# XRACER-SERIALS-R07.net
KiCad netlist of a schematic drawn in Altium Designer
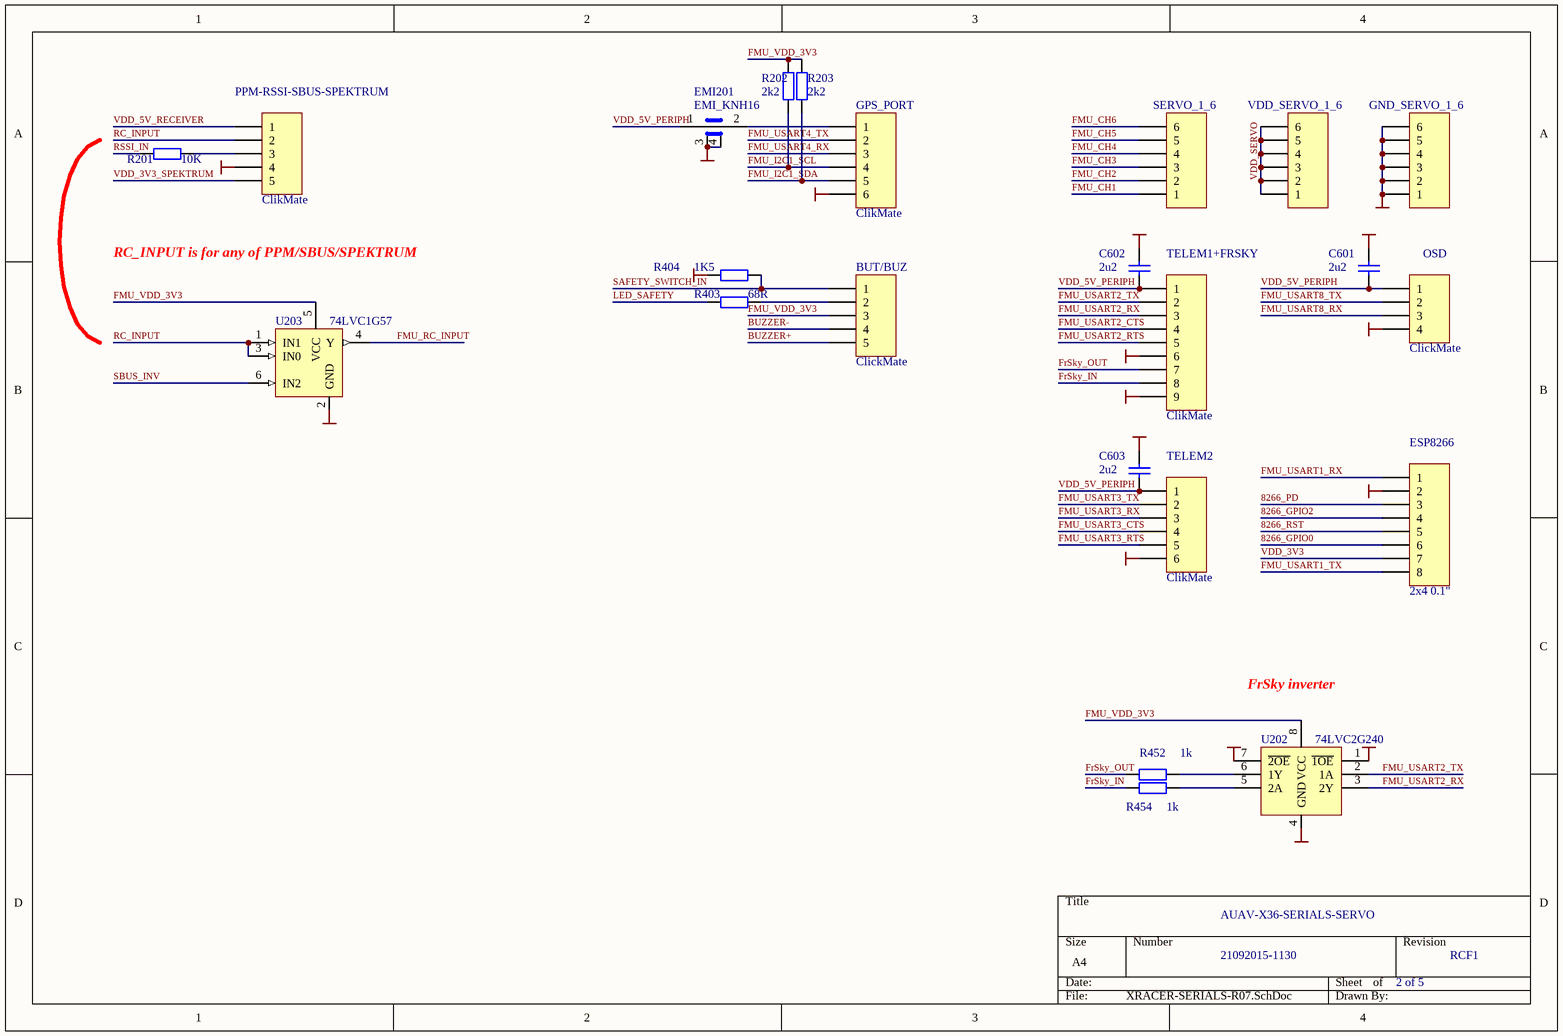
[diagram p0: XRACER-SERIALS-R07.SchDoc]

(export (version "E")
  (design (tool "Eeschema 10.0.6"))
  (components
    (comp (ref "BUT/BUZ")
      (value "ClickMate")
      (footprint "Molex_Clik_1.25_5H")
      (description "Header, 5-Pin")
      (fields (field (name "PUBLISHER") "Altium Limited"))
      (libsource (lib "Miscellaneous Connectors") (part "Header 5"))
    )
    (comp (ref "C601")
      (value "2u2")
      (footprint "0402A")
      (description "Capacitor")
      (fields (field (name "PUBLISHER") "Altium Limited"))
      (libsource (lib "Miscellaneous Devices") (part "Cap"))
    )
    (comp (ref "C602")
      (value "2u2")
      (footprint "0402A")
      (description "Capacitor")
      (fields (field (name "PUBLISHER") "Altium Limited"))
      (libsource (lib "Miscellaneous Devices") (part "Cap"))
    )
    (comp (ref "C603")
      (value "2u2")
      (footprint "0402A")
      (description "Capacitor")
      (fields (field (name "PUBLISHER") "Altium Limited"))
      (libsource (lib "Miscellaneous Devices") (part "Cap"))
    )
    (comp (ref "EMI201")
      (value "EMI_KNH16")
      (footprint "EMI_KNH16_0603")
      (libsource (lib "My_Altium") (part "EMI_KNH16"))
    )
    (comp (ref "ESP8266")
      (value "2x4 0.1\"")
      (footprint "2.54mm_2x4_SMD_female")
      (description "Header, 8-Pin")
      (fields (field (name "PUBLISHER") "Altium Limited"))
      (libsource (lib "Miscellaneous Connectors") (part "Header 8"))
    )
    (comp (ref "GND_SERVO_1_6")
      (value "Header 6")
      (footprint "HDR1X6")
      (description "Header, 6-Pin")
      (fields (field (name "PUBLISHER") "Altium Limited"))
      (libsource (lib "Miscellaneous Connectors") (part "Header 6"))
    )
    (comp (ref "GPS_PORT")
      (value "ClikMate")
      (footprint "Molex_Clok_1.25_6H")
      (description "Header, 6-Pin")
      (fields (field (name "PUBLISHER") "Altium Limited"))
      (libsource (lib "") (part "Header 6_1"))
    )
    (comp (ref "OSD")
      (value "ClickMate")
      (footprint "Molex_1.25_click_4")
      (description "Header, 4-Pin")
      (fields (field (name "PUBLISHER") "Altium Limited"))
      (libsource (lib "Miscellaneous Connectors") (part "Header 4"))
    )
    (comp (ref "PPM-RSSI-SBUS-SPEKTRUM")
      (value "ClikMate")
      (footprint "Molex_Clik_1.25_5H")
      (description "Header, 5-Pin")
      (fields (field (name "PUBLISHER") "Altium Limited"))
      (libsource (lib "Miscellaneous Connectors") (part "Header 5"))
    )
    (comp (ref "R201")
      (value "10K")
      (footprint "0402A")
      (description "Resistor")
      (fields (field (name "PUBLISHER") "Altium Limited"))
      (libsource (lib "") (part "Res2_1"))
    )
    (comp (ref "R202")
      (value "2k2")
      (footprint "0402A")
      (description "Resistor")
      (fields (field (name "PUBLISHER") "Altium Limited"))
      (libsource (lib "") (part "Res2_2"))
    )
    (comp (ref "R203")
      (value "2k2")
      (footprint "0402A")
      (description "Resistor")
      (fields (field (name "PUBLISHER") "Altium Limited"))
      (libsource (lib "") (part "Res2_2"))
    )
    (comp (ref "R403")
      (value "68R")
      (footprint "0402A")
      (description "Resistor")
      (fields (field (name "PUBLISHER") "Altium Limited"))
      (libsource (lib "") (part "Res2_1"))
    )
    (comp (ref "R404")
      (value "1K5")
      (footprint "0402A")
      (description "Resistor")
      (fields (field (name "PUBLISHER") "Altium Limited"))
      (libsource (lib "") (part "Res2_1"))
    )
    (comp (ref "R452")
      (value "1k")
      (footprint "0402A")
      (description "Resistor")
      (fields (field (name "PUBLISHER") "Altium Limited"))
      (libsource (lib "Miscellaneous Devices") (part "Res2"))
    )
    (comp (ref "R454")
      (value "1k")
      (footprint "0402A")
      (description "Resistor")
      (fields (field (name "PUBLISHER") "Altium Limited"))
      (libsource (lib "Miscellaneous Devices") (part "Res2"))
    )
    (comp (ref "SERVO_1_6")
      (value "Header 6")
      (footprint "HDR1X6")
      (description "Header, 6-Pin")
      (fields (field (name "PUBLISHER") "Altium Limited"))
      (libsource (lib "Miscellaneous Connectors") (part "Header 6"))
    )
    (comp (ref "TELEM1+FRSKY")
      (value "ClikMate")
      (footprint "Molex_Click_1.25_9H")
      (description "Header, 9-Pin")
      (fields (field (name "PUBLISHER") "Altium Limited"))
      (libsource (lib "Miscellaneous Connectors") (part "Header 9"))
    )
    (comp (ref "TELEM2")
      (value "ClikMate")
      (footprint "Molex_Clok_1.25_6H")
      (description "Header, 6-Pin")
      (fields (field (name "PUBLISHER") "Altium Limited"))
      (libsource (lib "") (part "Header 6_1"))
    )
    (comp (ref "U202")
      (value "74LVC2G240")
      (footprint "ssop-8")
      (libsource (lib "My_Altium") (part "74LVC2G240"))
    )
    (comp (ref "U203")
      (value "74LVC1G57")
      (footprint "sot323-6")
      (libsource (lib "My_Altium") (part "74LVC1G57"))
    )
    (comp (ref "VDD_SERVO_1_6")
      (value "Header 6")
      (footprint "HDR1X6")
      (description "Header, 6-Pin")
      (fields (field (name "PUBLISHER") "Altium Limited"))
      (libsource (lib "Miscellaneous Connectors") (part "Header 6"))
    )
  )
  (nets
    (net (code "1") (name "/8266_GPIO0") (class "Default")
      (node (ref "ESP8266") (pin "6") (pinfunction "6_6") (pintype "passive"))
    )
    (net (code "2") (name "/8266_GPIO2") (class "Default")
      (node (ref "ESP8266") (pin "4") (pinfunction "4_4") (pintype "passive"))
    )
    (net (code "3") (name "/8266_PD") (class "Default")
      (node (ref "ESP8266") (pin "3") (pinfunction "3_3") (pintype "passive"))
    )
    (net (code "4") (name "/8266_RST") (class "Default")
      (node (ref "ESP8266") (pin "5") (pinfunction "5_5") (pintype "passive"))
    )
    (net (code "5") (name "/BUZZER+") (class "Default")
      (node (ref "BUT/BUZ") (pin "5") (pinfunction "5_5") (pintype "passive"))
    )
    (net (code "6") (name "/BUZZER-") (class "Default")
      (node (ref "BUT/BUZ") (pin "4") (pinfunction "4_4") (pintype "passive"))
    )
    (net (code "7") (name "/FMU_CH1") (class "Default")
      (node (ref "SERVO_1_6") (pin "1") (pinfunction "1_1") (pintype "passive"))
    )
    (net (code "8") (name "/FMU_CH2") (class "Default")
      (node (ref "SERVO_1_6") (pin "2") (pinfunction "2_2") (pintype "passive"))
    )
    (net (code "9") (name "/FMU_CH3") (class "Default")
      (node (ref "SERVO_1_6") (pin "3") (pinfunction "3_3") (pintype "passive"))
    )
    (net (code "10") (name "/FMU_CH4") (class "Default")
      (node (ref "SERVO_1_6") (pin "4") (pinfunction "4_4") (pintype "passive"))
    )
    (net (code "11") (name "/FMU_CH5") (class "Default")
      (node (ref "SERVO_1_6") (pin "5") (pinfunction "5_5") (pintype "passive"))
    )
    (net (code "12") (name "/FMU_CH6") (class "Default")
      (node (ref "SERVO_1_6") (pin "6") (pinfunction "6_6") (pintype "passive"))
    )
    (net (code "13") (name "/FMU_I2C1_SCL") (class "Default")
      (node (ref "GPS_PORT") (pin "4") (pinfunction "4_4") (pintype "passive"))
      (node (ref "R202") (pin "2") (pinfunction "2_2") (pintype "passive"))
    )
    (net (code "14") (name "/FMU_I2C1_SDA") (class "Default")
      (node (ref "GPS_PORT") (pin "5") (pinfunction "5_5") (pintype "passive"))
      (node (ref "R203") (pin "2") (pinfunction "2_2") (pintype "passive"))
    )
    (net (code "15") (name "/FMU_RC_INPUT") (class "Default")
      (node (ref "U203") (pin "4") (pinfunction "Y_4") (pintype "output"))
    )
    (net (code "16") (name "/FMU_USART1_RX") (class "Default")
      (node (ref "ESP8266") (pin "1") (pinfunction "1_1") (pintype "passive"))
    )
    (net (code "17") (name "/FMU_USART1_TX") (class "Default")
      (node (ref "ESP8266") (pin "8") (pinfunction "8_8") (pintype "passive"))
    )
    (net (code "18") (name "/FMU_USART2_CTS") (class "Default")
      (node (ref "TELEM1+FRSKY") (pin "4") (pinfunction "4_4") (pintype "passive"))
    )
    (net (code "19") (name "/FMU_USART2_RTS") (class "Default")
      (node (ref "TELEM1+FRSKY") (pin "5") (pinfunction "5_5") (pintype "passive"))
    )
    (net (code "20") (name "/FMU_USART2_RX") (class "Default")
      (node (ref "TELEM1+FRSKY") (pin "3") (pinfunction "3_3") (pintype "passive"))
      (node (ref "U202") (pin "3") (pinfunction "2Y_3") (pintype "passive"))
    )
    (net (code "21") (name "/FMU_USART2_TX") (class "Default")
      (node (ref "TELEM1+FRSKY") (pin "2") (pinfunction "2_2") (pintype "passive"))
      (node (ref "U202") (pin "2") (pinfunction "1A_2") (pintype "passive"))
    )
    (net (code "22") (name "/FMU_USART3_CTS") (class "Default")
      (node (ref "TELEM2") (pin "4") (pinfunction "4_4") (pintype "passive"))
    )
    (net (code "23") (name "/FMU_USART3_RTS") (class "Default")
      (node (ref "TELEM2") (pin "5") (pinfunction "5_5") (pintype "passive"))
    )
    (net (code "24") (name "/FMU_USART3_RX") (class "Default")
      (node (ref "TELEM2") (pin "3") (pinfunction "3_3") (pintype "passive"))
    )
    (net (code "25") (name "/FMU_USART3_TX") (class "Default")
      (node (ref "TELEM2") (pin "2") (pinfunction "2_2") (pintype "passive"))
    )
    (net (code "26") (name "/FMU_USART4_RX") (class "Default")
      (node (ref "GPS_PORT") (pin "3") (pinfunction "3_3") (pintype "passive"))
    )
    (net (code "27") (name "/FMU_USART4_TX") (class "Default")
      (node (ref "GPS_PORT") (pin "2") (pinfunction "2_2") (pintype "passive"))
    )
    (net (code "28") (name "/FMU_USART8_RX") (class "Default")
      (node (ref "OSD") (pin "3") (pinfunction "3_3") (pintype "passive"))
    )
    (net (code "29") (name "/FMU_USART8_TX") (class "Default")
      (node (ref "OSD") (pin "2") (pinfunction "2_2") (pintype "passive"))
    )
    (net (code "30") (name "/FMU_VDD_3V3") (class "Default")
      (node (ref "BUT/BUZ") (pin "3") (pinfunction "3_3") (pintype "passive"))
      (node (ref "R202") (pin "1") (pinfunction "1_1") (pintype "passive"))
      (node (ref "R203") (pin "1") (pinfunction "1_1") (pintype "passive"))
      (node (ref "U202") (pin "8") (pinfunction "VCC_8") (pintype "passive"))
      (node (ref "U203") (pin "5") (pinfunction "VCC_5") (pintype "power_in"))
    )
    (net (code "31") (name "/FrSky_IN") (class "Default")
      (node (ref "R454") (pin "1") (pinfunction "1_1") (pintype "passive"))
      (node (ref "TELEM1+FRSKY") (pin "8") (pinfunction "8_8") (pintype "passive"))
    )
    (net (code "32") (name "/FrSky_OUT") (class "Default")
      (node (ref "R452") (pin "1") (pinfunction "1_1") (pintype "passive"))
      (node (ref "TELEM1+FRSKY") (pin "7") (pinfunction "7_7") (pintype "passive"))
    )
    (net (code "33") (name "/LED_SAFETY") (class "Default")
      (node (ref "R403") (pin "2") (pinfunction "2_2") (pintype "passive"))
    )
    (net (code "34") (name "/RC_INPUT") (class "Default")
      (node (ref "PPM-RSSI-SBUS-SPEKTRUM") (pin "2") (pinfunction "2_2") (pintype "passive"))
      (node (ref "U203") (pin "1") (pinfunction "IN1_1") (pintype "input"))
      (node (ref "U203") (pin "3") (pinfunction "IN0_3") (pintype "input"))
    )
    (net (code "35") (name "/RSSI_IN") (class "Default")
      (node (ref "R201") (pin "2") (pinfunction "2_2") (pintype "passive"))
    )
    (net (code "36") (name "/SAFETY_SWITCH_IN") (class "Default")
      (node (ref "BUT/BUZ") (pin "1") (pinfunction "1_1") (pintype "passive"))
      (node (ref "R404") (pin "1") (pinfunction "1_1") (pintype "passive"))
    )
    (net (code "37") (name "/SBUS_INV") (class "Default")
      (node (ref "U203") (pin "6") (pinfunction "IN2_6") (pintype "input"))
    )
    (net (code "38") (name "/VDD_3V3") (class "Default")
      (node (ref "ESP8266") (pin "7") (pinfunction "7_7") (pintype "passive"))
    )
    (net (code "39") (name "/VDD_3V3_SPEKTRUM") (class "Default")
      (node (ref "PPM-RSSI-SBUS-SPEKTRUM") (pin "5") (pinfunction "5_5") (pintype "passive"))
    )
    (net (code "40") (name "/VDD_5V_PERIPH") (class "Default")
      (node (ref "C601") (pin "1") (pinfunction "1_1") (pintype "passive"))
      (node (ref "C602") (pin "1") (pinfunction "1_1") (pintype "passive"))
      (node (ref "C603") (pin "1") (pinfunction "1_1") (pintype "passive"))
      (node (ref "EMI201") (pin "1") (pinfunction "L1_1") (pintype "passive"))
      (node (ref "OSD") (pin "1") (pinfunction "1_1") (pintype "passive"))
      (node (ref "TELEM1+FRSKY") (pin "1") (pinfunction "1_1") (pintype "passive"))
      (node (ref "TELEM2") (pin "1") (pinfunction "1_1") (pintype "passive"))
    )
    (net (code "41") (name "/VDD_5V_RECEIVER") (class "Default")
      (node (ref "PPM-RSSI-SBUS-SPEKTRUM") (pin "1") (pinfunction "1_1") (pintype "passive"))
    )
    (net (code "42") (name "/VDD_SERVO") (class "Default")
      (node (ref "VDD_SERVO_1_6") (pin "1") (pinfunction "1_1") (pintype "passive"))
      (node (ref "VDD_SERVO_1_6") (pin "2") (pinfunction "2_2") (pintype "passive"))
      (node (ref "VDD_SERVO_1_6") (pin "3") (pinfunction "3_3") (pintype "passive"))
      (node (ref "VDD_SERVO_1_6") (pin "4") (pinfunction "4_4") (pintype "passive"))
      (node (ref "VDD_SERVO_1_6") (pin "5") (pinfunction "5_5") (pintype "passive"))
      (node (ref "VDD_SERVO_1_6") (pin "6") (pinfunction "6_6") (pintype "passive"))
    )
    (net (code "43") (name "GND") (class "Default")
      (node (ref "C601") (pin "2") (pinfunction "2_2") (pintype "passive"))
      (node (ref "C602") (pin "2") (pinfunction "2_2") (pintype "passive"))
      (node (ref "C603") (pin "2") (pinfunction "2_2") (pintype "passive"))
      (node (ref "EMI201") (pin "3") (pinfunction "G_3") (pintype "power_in"))
      (node (ref "EMI201") (pin "4") (pinfunction "G_4") (pintype "passive"))
      (node (ref "ESP8266") (pin "2") (pinfunction "2_2") (pintype "passive"))
      (node (ref "GND_SERVO_1_6") (pin "1") (pinfunction "1_1") (pintype "passive"))
      (node (ref "GND_SERVO_1_6") (pin "2") (pinfunction "2_2") (pintype "passive"))
      (node (ref "GND_SERVO_1_6") (pin "3") (pinfunction "3_3") (pintype "passive"))
      (node (ref "GND_SERVO_1_6") (pin "4") (pinfunction "4_4") (pintype "passive"))
      (node (ref "GND_SERVO_1_6") (pin "5") (pinfunction "5_5") (pintype "passive"))
      (node (ref "GND_SERVO_1_6") (pin "6") (pinfunction "6_6") (pintype "passive"))
      (node (ref "GPS_PORT") (pin "6") (pinfunction "6_6") (pintype "passive"))
      (node (ref "OSD") (pin "4") (pinfunction "4_4") (pintype "passive"))
      (node (ref "PPM-RSSI-SBUS-SPEKTRUM") (pin "4") (pinfunction "4_4") (pintype "passive"))
      (node (ref "R404") (pin "2") (pinfunction "2_2") (pintype "passive"))
      (node (ref "TELEM1+FRSKY") (pin "6") (pinfunction "6_6") (pintype "passive"))
      (node (ref "TELEM1+FRSKY") (pin "9") (pinfunction "9_9") (pintype "passive"))
      (node (ref "TELEM2") (pin "6") (pinfunction "6_6") (pintype "passive"))
      (node (ref "U202") (pin "1") (pinfunction "~{1OE}_1") (pintype "passive"))
      (node (ref "U202") (pin "4") (pinfunction "GND_4") (pintype "passive"))
      (node (ref "U202") (pin "7") (pinfunction "~{2OE}_7") (pintype "passive"))
      (node (ref "U203") (pin "2") (pinfunction "GND_2") (pintype "power_in"))
    )
    (net (code "44") (name "Net-(BUT/BUZ-Pad2)") (class "Default")
      (node (ref "BUT/BUZ") (pin "2") (pinfunction "2_2") (pintype "passive"))
      (node (ref "R403") (pin "1") (pinfunction "1_1") (pintype "passive"))
    )
    (net (code "45") (name "Net-(EMI201-L2)") (class "Default")
      (node (ref "EMI201") (pin "2") (pinfunction "L2_2") (pintype "passive"))
      (node (ref "GPS_PORT") (pin "1") (pinfunction "1_1") (pintype "passive"))
    )
    (net (code "46") (name "Net-(PPM-RSSI-SBUS-SPEKTRUM-Pad3)") (class "Default")
      (node (ref "PPM-RSSI-SBUS-SPEKTRUM") (pin "3") (pinfunction "3_3") (pintype "passive"))
      (node (ref "R201") (pin "1") (pinfunction "1_1") (pintype "passive"))
    )
    (net (code "47") (name "Net-(U202-1Y)") (class "Default")
      (node (ref "R452") (pin "2") (pinfunction "2_2") (pintype "passive"))
      (node (ref "U202") (pin "6") (pinfunction "1Y_6") (pintype "passive"))
    )
    (net (code "48") (name "Net-(U202-2A)") (class "Default")
      (node (ref "R454") (pin "2") (pinfunction "2_2") (pintype "passive"))
      (node (ref "U202") (pin "5") (pinfunction "2A_5") (pintype "passive"))
    )
  )
)
